# Sheet1.net
KiCad netlist of a schematic drawn in Altium Designer
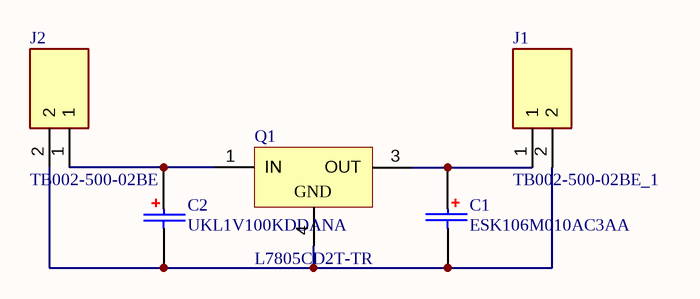
[diagram p0: Sheet1.SchDoc]

(export (version "E")
  (design (tool "Eeschema 10.0.6"))
  (components
    (comp (ref "C1")
      (value "ESK106M010AC3AA")
      (footprint "ESK106M010AC3AA")
      (fields (field (name "MANUFACTURER") "Yageo Group"))
      (libsource (lib "Schlib2") (part "ESK106M010AC3AA"))
    )
    (comp (ref "C2")
      (value "UKL1V100KDDANA")
      (footprint "CAP_UKL_5X11_NCH")
      (description "Aluminum Electrolytic Capacitor, 10UF, 35V, 10%, Radial")
      (fields (field (name "MANUFACTURER") "Nichicon") (field (name "TOLERANCE") "10%"))
      (libsource (lib "Schlib2") (part "UKL1V100KDDANA"))
    )
    (comp (ref "J1")
      (value "TB002-500-02BE_1")
      (footprint "CUI_TB002-500-02BE - duplicate")
      (description "Barrier Strip Terminal Block 15A 3.31Mm2 1 Row Rohs Compliant: Yes ¦Same Sky TB002-500-02BE")
      (fields
        (field (name "MANUFACTURER") "Same Sky")
        (field (name "MANUFACTURER PART NUMBER") "TB002-500-02BE")
      )
      (libsource (lib "Schlib2") (part "TB002-500-02BE_1"))
    )
    (comp (ref "J2")
      (value "TB002-500-02BE")
      (footprint "CUI_TB002-500-02BE")
      (description "Barrier Strip Terminal Block 15A 3.31Mm2 1 Row Rohs Compliant: Yes ¦Same Sky TB002-500-02BE")
      (fields (field (name "MANUFACTURER") "Same Sky"))
      (libsource (lib "Schlib2") (part "TB002-500-02BE"))
    )
    (comp (ref "Q1")
      (value "L7805CD2T-TR")
      (footprint "3")
      (description "Linear Voltage Regulator, Fixed, Positive Output, 35 V, 5 V, 1.5 A, 3 Pins, TO-263 (D2PAK)")
      (fields (field (name "MANUFACTURER") "STMicroelectronics"))
      (libsource (lib "Schlib2") (part "L7805CD2T-TR"))
    )
  )
  (nets
    (net (code "1") (name "Net-(Q1-GND)") (class "Default")
      (node (ref "C1") (pin "2") (pinfunction "2_2") (pintype "passive"))
      (node (ref "C2") (pin "2") (pinfunction "2_2") (pintype "passive"))
      (node (ref "J1") (pin "2") (pinfunction "2_2") (pintype "passive"))
      (node (ref "J2") (pin "2") (pinfunction "2_2") (pintype "passive"))
      (node (ref "Q1") (pin "4") (pinfunction "GND_4") (pintype "power_in"))
    )
    (net (code "2") (name "Net-(Q1-IN)") (class "Default")
      (node (ref "C2") (pin "1") (pinfunction "1_1") (pintype "passive"))
      (node (ref "J2") (pin "1") (pinfunction "1_1") (pintype "passive"))
      (node (ref "Q1") (pin "1") (pinfunction "IN_1") (pintype "power_in"))
    )
    (net (code "3") (name "Net-(Q1-OUT)") (class "Default")
      (node (ref "C1") (pin "1") (pinfunction "1_1") (pintype "passive"))
      (node (ref "J1") (pin "1") (pinfunction "1_1") (pintype "passive"))
      (node (ref "Q1") (pin "3") (pinfunction "OUT_3") (pintype "power_in"))
    )
  )
)
